# 20-Power-P1V8.net
KiCad netlist of a schematic drawn in Altium Designer
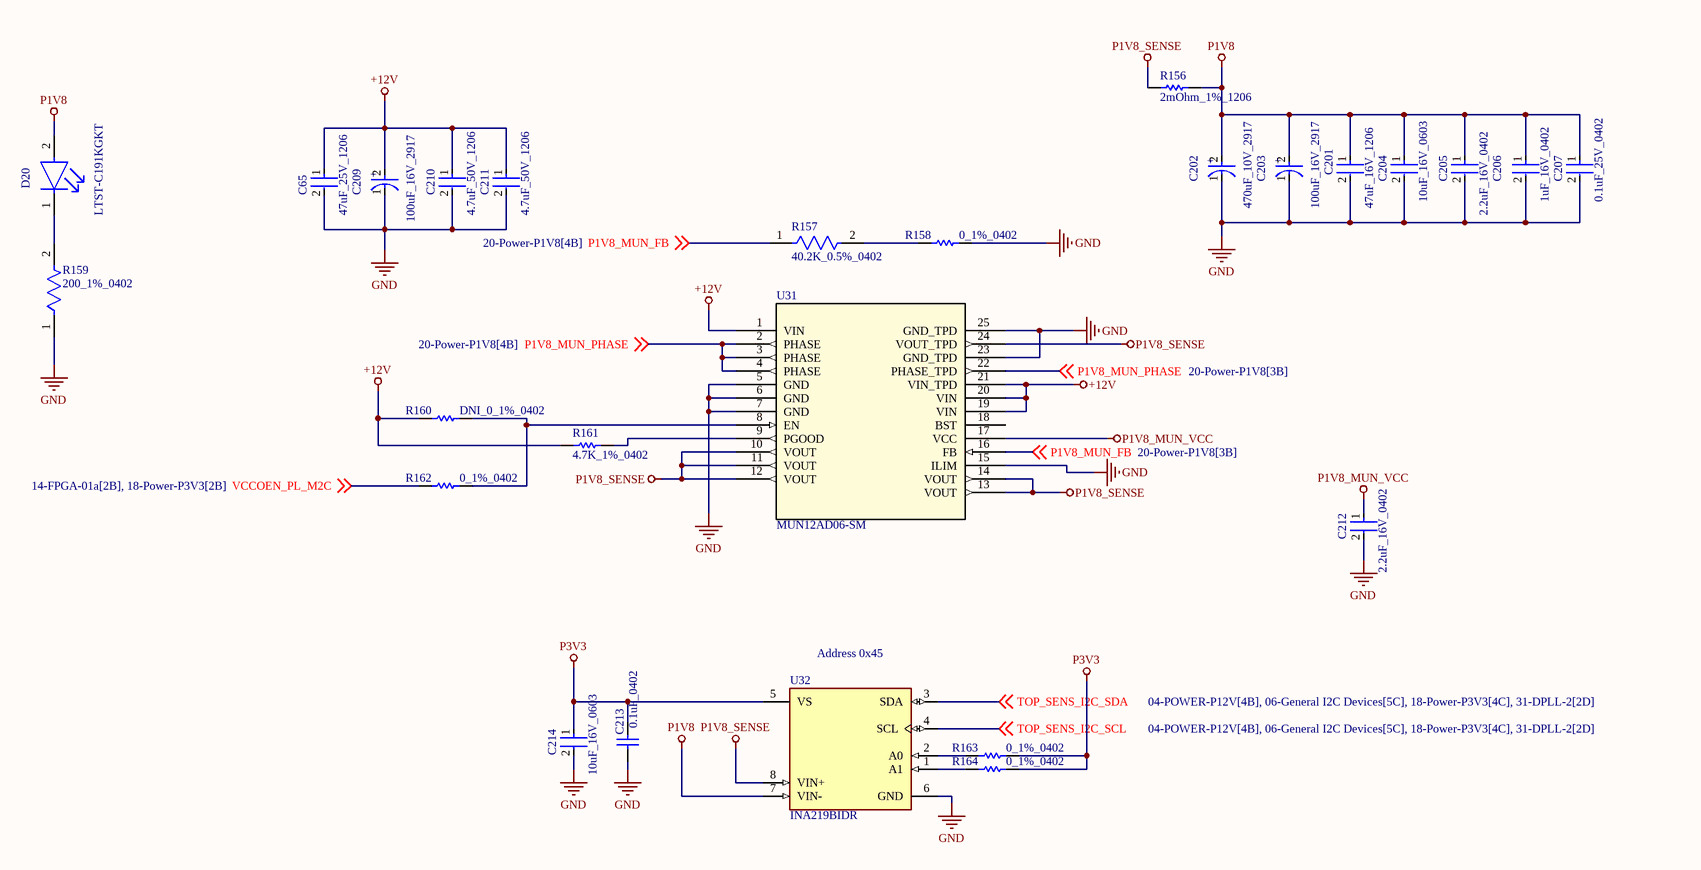
[diagram p0: 20-Power-P1V8.SchDoc]

(export (version "E")
  (design (tool "Eeschema 10.0.6"))
  (components
    (comp (ref "C65")
      (value "47uF_25V_1206")
      (footprint "FP-C3216-160-0_2-MFG")
      (description "Multilayer Ceramic Capacitors 47uF ±20% 25V X5R SMD 1206")
      (fields (field (name "VOLTAGE") "25V") (field (name "TOLERANCE") "20%"))
      (libsource (lib "Altium Content Vault") (part "11868f565c42a9108669ba33697ecf6"))
    )
    (comp (ref "C201")
      (value "47uF_16V_1206")
      (footprint "FP-C3216-160-0_2-MFG")
      (description "Multilayer Ceramic Capacitors 47uF ±20% 16V X5R SMD 1206")
      (fields (field (name "TOLERANCE") "20%"))
      (libsource (lib "Altium Content Vault") (part "11868f565c42a9108669ba33697ecf6"))
    )
    (comp (ref "C202")
      (value "470uF_10V_2917")
      (footprint "FP-TAJE-MFG")
      (description "470uF 10V  ±10% 500mΩ 2917  SMD Tantalum Capacitor")
      (fields (field (name "TOLERANCE") "10%") (field (name "VOLTAGE") "10V"))
      (libsource (lib "Altium Content Vault") (part "203bc49f2ac43e59fd269a8c329ed05"))
    )
    (comp (ref "C203")
      (value "100uF_16V_2917")
      (footprint "FP-T495D107K016ATE125-MFG")
      (description "CAP TANT 100UF 10% 16V 2917")
      (fields (field (name "VOLTAGE") "16V") (field (name "TOLERANCE") "10%"))
      (libsource (lib "Altium Content Vault") (part "a00bbbee19879c290e62620ae7e47b1"))
    )
    (comp (ref "C204")
      (value "10uF_16V_0603")
      (footprint "FP-0603-L_1_6_0_2-W_0_8_0-MFG")
      (description "Multilayer Ceramic Capacitor 10uF 16V X5R 20% SMD 0603 T/R")
      (fields (field (name "TOLERANCE") "20%"))
      (libsource (lib "Altium Content Vault") (part "b4654b650e69147ec39a6b967a45e02"))
    )
    (comp (ref "C205")
      (value "2.2uF_16V_0402")
      (footprint "FP-C1005-050-0_05-IPC_A")
      (description "Multilayer Ceramic Capacitors 2.2μF ±10% 16V X5R SMD 0402")
      (fields (field (name "TOLERANCE") "10%"))
      (libsource (lib "Altium Content Vault") (part "b4654b650e69147ec39a6b967a45e02"))
    )
    (comp (ref "C206")
      (value "1uF_16V_0402")
      (footprint "FP-0402-L_1_0_0_05-W_0_5-IPC_A")
      (description "None")
      (fields (field (name "TOLERANCE") "10%"))
      (libsource (lib "Altium Content Vault") (part "b4654b650e69147ec39a6b967a45e02"))
    )
    (comp (ref "C207")
      (value "0.1uF_25V_0402")
      (footprint "FP-0402-L_1_0_1-W_0_5_0_1-IPC_C")
      (description "General Purpose Ceramic Capacitor, 0402, 100nF, 10%, X7R, 15%, 25V")
      (fields (field (name "VOLTAGE") "25V") (field (name "TOLERANCE") "10%"))
      (libsource (lib "Altium Content Vault") (part "b4654b650e69147ec39a6b967a45e02"))
    )
    (comp (ref "C209")
      (value "100uF_16V_2917")
      (footprint "FP-T495D107K016ATE125-MFG")
      (description "CAP TANT 100UF 10% 16V 2917")
      (fields (field (name "VOLTAGE") "16V") (field (name "TOLERANCE") "10%"))
      (libsource (lib "Altium Content Vault") (part "a00bbbee19879c290e62620ae7e47b1"))
    )
    (comp (ref "C210")
      (value "4.7uF_50V_1206")
      (footprint "FP-GRM31C-0_2-e0_3_0_8-IPC_C")
      (description "Chip Multilayer Ceramic Capacitors for General Purpose, 1206, 4.7uF, X7R, 15%, 10%, 50V")
      (fields (field (name "VOLTAGE") "50V") (field (name "TOLERANCE") "10%"))
      (libsource (lib "Altium Content Vault") (part "02cd4be3c70576c341d710602a673aa"))
    )
    (comp (ref "C211")
      (value "4.7uF_50V_1206")
      (footprint "FP-GRM31C-0_2-e0_3_0_8-IPC_C")
      (description "Chip Multilayer Ceramic Capacitors for General Purpose, 1206, 4.7uF, X7R, 15%, 10%, 50V")
      (fields (field (name "VOLTAGE") "50V") (field (name "TOLERANCE") "10%"))
      (libsource (lib "Altium Content Vault") (part "02cd4be3c70576c341d710602a673aa"))
    )
    (comp (ref "C212")
      (value "2.2uF_16V_0402")
      (footprint "FP-C1005-050-0_05-IPC_A")
      (description "Multilayer Ceramic Capacitors 2.2μF ±10% 16V X5R SMD 0402")
      (fields (field (name "TOLERANCE") "10%"))
      (libsource (lib "Altium Content Vault") (part "b4654b650e69147ec39a6b967a45e02"))
    )
    (comp (ref "C213")
      (value "0.1uF_0402")
      (footprint "CAPC1005X56X25NL10T15")
      (fields
        (field (name "PART NUMBER") "LD02YD104KAB2A")
        (field (name "MANUFACTURER") "AVX Interconnect / Elco")
      )
      (libsource (lib "Altium Content Vault") (part "CAP"))
    )
    (comp (ref "C214")
      (value "10uF_16V_0603")
      (footprint "FP-0603-L_1_6_0_2-W_0_8_0-MFG")
      (description "Multilayer Ceramic Capacitor 10uF 16V X5R 20% SMD 0603 T/R")
      (fields (field (name "TOLERANCE") "20%"))
      (libsource (lib "Altium Content Vault") (part "b4654b650e69147ec39a6b967a45e02"))
    )
    (comp (ref "D20")
      (value "LTST-C191KGKT")
      (footprint "FP-LTST-C191KGKT-MFG")
      (description "LED GREEN CLEAR SMD")
      (libsource (lib "Altium Content Vault") (part "8706943c75ba83719d021d2fdc84c58"))
    )
    (comp (ref "R156")
      (value "2mOhm_1%_1206")
      (footprint "RESC3216X89X64NL25T25")
      (fields (field (name "MANUFACTURER") "Vishay Dale") (field (name "PART NUMBER") "WSL12062L000FEA18"))
      (libsource (lib "Altium Content Vault") (part "RES"))
    )
    (comp (ref "R157")
      (value "40.2K_0.5%_0402")
      (footprint "FP-RR0510-MFG")
      (description "40.2kΩ ±0.5% 0.0625W 1/16W Chip Resistor 0402 (1005 Metric) Thin Film")
      (fields (field (name "TOLERANCE") "0.5%"))
      (libsource (lib "Altium Content Vault") (part "1029c3af85768c4190bb7ad29bc67b5"))
    )
    (comp (ref "R158")
      (value "0_1%_0402")
      (footprint "RESC1005X40X25LL05T05")
      (description "Chip Resistor, 0 Ohm, 0.1 W, -55 to 155 degC, 0402 (1005 Metric), RoHS, Tape and Reel")
      (fields (field (name "MANUFACTURER") "Panasonic") (field (name "TOLERANCE") "5%"))
      (libsource (lib "Altium Content Vault") (part "RES-2"))
    )
    (comp (ref "R159")
      (value "200_1%_0402")
      (footprint "FP-ERJ2RK-IPC_A")
      (description "RES SMD 200 OHM 1% 1/10W 0402")
      (fields (field (name "TOLERANCE") "1%"))
      (libsource (lib "Altium Content Vault") (part "1029c3af85768c4190bb7ad29bc67b5"))
    )
    (comp (ref "R160")
      (value "DNI_0_1%_0402")
      (footprint "RESC1005X40X25LL05T05")
      (description "Chip Resistor, 0 Ohm, 0.1 W, -55 to 155 degC, 0402 (1005 Metric), RoHS, Tape and Reel")
      (fields (field (name "MANUFACTURER") "Panasonic") (field (name "TOLERANCE") "5%"))
      (libsource (lib "Altium Content Vault") (part "RES-2"))
    )
    (comp (ref "R161")
      (value "4.7K_1%_0402")
      (footprint "RESC1005X40X25NL10T10")
      (fields (field (name "MANUFACTURER") "Bourns") (field (name "PART NUMBER") "CR0402-FX-4701GLF"))
      (libsource (lib "Altium Content Vault") (part "RES"))
    )
    (comp (ref "R162")
      (value "0_1%_0402")
      (footprint "RESC1005X40X25LL05T05")
      (description "Chip Resistor, 0 Ohm, 0.1 W, -55 to 155 degC, 0402 (1005 Metric), RoHS, Tape and Reel")
      (fields (field (name "MANUFACTURER") "Panasonic") (field (name "TOLERANCE") "5%"))
      (libsource (lib "Altium Content Vault") (part "RES-2"))
    )
    (comp (ref "R163")
      (value "0_1%_0402")
      (footprint "RESC1005X40X25LL05T05")
      (description "Chip Resistor, 0 Ohm, 0.1 W, -55 to 155 degC, 0402 (1005 Metric), RoHS, Tape and Reel")
      (fields (field (name "MANUFACTURER") "Panasonic") (field (name "TOLERANCE") "5%"))
      (libsource (lib "Altium Content Vault") (part "RES-2"))
    )
    (comp (ref "R164")
      (value "0_1%_0402")
      (footprint "RESC1005X40X25LL05T05")
      (description "Chip Resistor, 0 Ohm, 0.1 W, -55 to 155 degC, 0402 (1005 Metric), RoHS, Tape and Reel")
      (fields (field (name "MANUFACTURER") "Panasonic") (field (name "TOLERANCE") "5%"))
      (libsource (lib "Altium Content Vault") (part "RES-2"))
    )
    (comp (ref "U31")
      (value "MUN12AD06-SM")
      (footprint "MUN12AD06-SM_CYN")
      (description "No Description Available")
      (libsource (lib "MUN12AD06-SM") (part "MUN12AD06-SM"))
    )
    (comp (ref "U32")
      (value "INA219BIDR")
      (footprint "FP-D0008A-MFG")
      (description "IC MONITOR PWR/CURR BIDIR 8-SOIC")
      (libsource (lib "Altium Content Vault") (part "41cc1aee4cbc9fa2660a15773fa0e79"))
    )
  )
  (nets
    (net (code "1") (name "+12V") (class "Default")
      (node (ref "C209") (pin "2") (pinfunction "A_2") (pintype "passive"))
      (node (ref "C210") (pin "1") (pinfunction "1_1") (pintype "passive"))
      (node (ref "C211") (pin "1") (pinfunction "1_1") (pintype "passive"))
      (node (ref "C65") (pin "1") (pinfunction "1_1") (pintype "passive"))
      (node (ref "R160") (pin "1") (pinfunction "1_1") (pintype "passive"))
      (node (ref "R161") (pin "2") (pinfunction "2_2") (pintype "passive"))
      (node (ref "U31") (pin "1") (pinfunction "VIN_1") (pintype "power_in"))
      (node (ref "U31") (pin "19") (pinfunction "VIN_19") (pintype "power_in"))
      (node (ref "U31") (pin "20") (pinfunction "VIN_20") (pintype "power_in"))
      (node (ref "U31") (pin "21") (pinfunction "VIN_TPD_21") (pintype "power_in"))
    )
    (net (code "2") (name "GND") (class "Default")
      (node (ref "C201") (pin "2") (pinfunction "2_2") (pintype "passive"))
      (node (ref "C202") (pin "1") (pinfunction "C_1") (pintype "passive"))
      (node (ref "C203") (pin "1") (pinfunction "C_1") (pintype "passive"))
      (node (ref "C204") (pin "2") (pinfunction "2_2") (pintype "passive"))
      (node (ref "C205") (pin "2") (pinfunction "2_2") (pintype "passive"))
      (node (ref "C206") (pin "2") (pinfunction "2_2") (pintype "passive"))
      (node (ref "C207") (pin "2") (pinfunction "2_2") (pintype "passive"))
      (node (ref "C209") (pin "1") (pinfunction "C_1") (pintype "passive"))
      (node (ref "C210") (pin "2") (pinfunction "2_2") (pintype "passive"))
      (node (ref "C211") (pin "2") (pinfunction "2_2") (pintype "passive"))
      (node (ref "C212") (pin "2") (pinfunction "2_2") (pintype "passive"))
      (node (ref "C213") (pin "1") (pinfunction "1_1") (pintype "passive"))
      (node (ref "C214") (pin "2") (pinfunction "2_2") (pintype "passive"))
      (node (ref "C65") (pin "2") (pinfunction "2_2") (pintype "passive"))
      (node (ref "R158") (pin "2") (pinfunction "2_2") (pintype "passive"))
      (node (ref "R159") (pin "1") (pinfunction "1_1") (pintype "passive"))
      (node (ref "U31") (pin "15") (pinfunction "ILIM_15") (pintype "passive"))
      (node (ref "U31") (pin "23") (pinfunction "GND_TPD_23") (pintype "power_in"))
      (node (ref "U31") (pin "25") (pinfunction "GND_TPD_25") (pintype "power_in"))
      (node (ref "U31") (pin "5") (pinfunction "GND_5") (pintype "power_in"))
      (node (ref "U31") (pin "6") (pinfunction "GND_6") (pintype "power_in"))
      (node (ref "U31") (pin "7") (pinfunction "GND_7") (pintype "power_in"))
      (node (ref "U32") (pin "6") (pinfunction "GND_6") (pintype "power_in"))
    )
    (net (code "3") (name "Net-(D20-C)") (class "Default")
      (node (ref "D20") (pin "1") (pinfunction "C_1") (pintype "passive"))
      (node (ref "R159") (pin "2") (pinfunction "2_2") (pintype "passive"))
    )
    (net (code "4") (name "Net-(R157-Pad2)") (class "Default")
      (node (ref "R157") (pin "2") (pinfunction "2_2") (pintype "passive"))
      (node (ref "R158") (pin "1") (pinfunction "1_1") (pintype "passive"))
    )
    (net (code "5") (name "Net-(U31-EN)") (class "Default")
      (node (ref "R160") (pin "2") (pinfunction "2_2") (pintype "passive"))
      (node (ref "R162") (pin "2") (pinfunction "2_2") (pintype "passive"))
      (node (ref "U31") (pin "8") (pinfunction "EN_8") (pintype "input"))
    )
    (net (code "6") (name "Net-(U31-PGOOD)") (class "Default")
      (node (ref "R161") (pin "1") (pinfunction "1_1") (pintype "passive"))
      (node (ref "U31") (pin "9") (pinfunction "PGOOD_9") (pintype "output"))
    )
    (net (code "7") (name "Net-(U32-A0)") (class "Default")
      (node (ref "R163") (pin "1") (pinfunction "1_1") (pintype "passive"))
      (node (ref "U32") (pin "2") (pinfunction "A0_2") (pintype "input"))
    )
    (net (code "8") (name "Net-(U32-A1)") (class "Default")
      (node (ref "R164") (pin "1") (pinfunction "1_1") (pintype "passive"))
      (node (ref "U32") (pin "1") (pinfunction "A1_1") (pintype "input"))
    )
    (net (code "9") (name "P1V8") (class "Default")
      (node (ref "C201") (pin "1") (pinfunction "1_1") (pintype "passive"))
      (node (ref "C202") (pin "2") (pinfunction "A_2") (pintype "passive"))
      (node (ref "C203") (pin "2") (pinfunction "A_2") (pintype "passive"))
      (node (ref "C204") (pin "1") (pinfunction "1_1") (pintype "passive"))
      (node (ref "C205") (pin "1") (pinfunction "1_1") (pintype "passive"))
      (node (ref "C206") (pin "1") (pinfunction "1_1") (pintype "passive"))
      (node (ref "C207") (pin "1") (pinfunction "1_1") (pintype "passive"))
      (node (ref "D20") (pin "2") (pinfunction "A_2") (pintype "passive"))
      (node (ref "R156") (pin "2") (pinfunction "2_2") (pintype "passive"))
      (node (ref "U32") (pin "7") (pinfunction "VIN-_7") (pintype "input"))
    )
    (net (code "10") (name "P1V8_MUN_FB") (class "Default")
      (node (ref "R157") (pin "1") (pinfunction "1_1") (pintype "passive"))
      (node (ref "U31") (pin "16") (pinfunction "FB_16") (pintype "input"))
    )
    (net (code "11") (name "P1V8_MUN_PHASE") (class "Default")
      (node (ref "U31") (pin "2") (pinfunction "PHASE_2") (pintype "output"))
      (node (ref "U31") (pin "22") (pinfunction "PHASE_TPD_22") (pintype "output"))
      (node (ref "U31") (pin "3") (pinfunction "PHASE_3") (pintype "output"))
      (node (ref "U31") (pin "4") (pinfunction "PHASE_4") (pintype "output"))
    )
    (net (code "12") (name "P1V8_MUN_VCC") (class "Default")
      (node (ref "C212") (pin "1") (pinfunction "1_1") (pintype "passive"))
      (node (ref "U31") (pin "17") (pinfunction "VCC_17") (pintype "power_in"))
    )
    (net (code "13") (name "P1V8_SENSE") (class "Default")
      (node (ref "R156") (pin "1") (pinfunction "1_1") (pintype "passive"))
      (node (ref "U31") (pin "10") (pinfunction "VOUT_10") (pintype "output"))
      (node (ref "U31") (pin "11") (pinfunction "VOUT_11") (pintype "output"))
      (node (ref "U31") (pin "12") (pinfunction "VOUT_12") (pintype "output"))
      (node (ref "U31") (pin "13") (pinfunction "VOUT_13") (pintype "output"))
      (node (ref "U31") (pin "14") (pinfunction "VOUT_14") (pintype "output"))
      (node (ref "U31") (pin "24") (pinfunction "VOUT_TPD_24") (pintype "output"))
      (node (ref "U32") (pin "8") (pinfunction "VIN+_8") (pintype "input"))
    )
    (net (code "14") (name "P3V3") (class "Default")
      (node (ref "C213") (pin "2") (pinfunction "2_2") (pintype "passive"))
      (node (ref "C214") (pin "1") (pinfunction "1_1") (pintype "passive"))
      (node (ref "R163") (pin "2") (pinfunction "2_2") (pintype "passive"))
      (node (ref "R164") (pin "2") (pinfunction "2_2") (pintype "passive"))
      (node (ref "U32") (pin "5") (pinfunction "VS_5") (pintype "power_in"))
    )
    (net (code "15") (name "TOP_SENS_I2C_SCL") (class "Default")
      (node (ref "U32") (pin "4") (pinfunction "SCL_4") (pintype "bidirectional"))
    )
    (net (code "16") (name "TOP_SENS_I2C_SDA") (class "Default")
      (node (ref "U32") (pin "3") (pinfunction "SDA_3") (pintype "bidirectional"))
    )
    (net (code "17") (name "VCCOEN_PL_M2C") (class "Default")
      (node (ref "R162") (pin "1") (pinfunction "1_1") (pintype "passive"))
    )
    (net (code "18") (name "unconnected-(U31-BST-Pad18)") (class "Default")
      (node (ref "U31") (pin "18") (pinfunction "BST_18") (pintype "power_in"))
    )
  )
)
